# DAC_Interface.net
KiCad netlist of a schematic drawn in Altium Designer
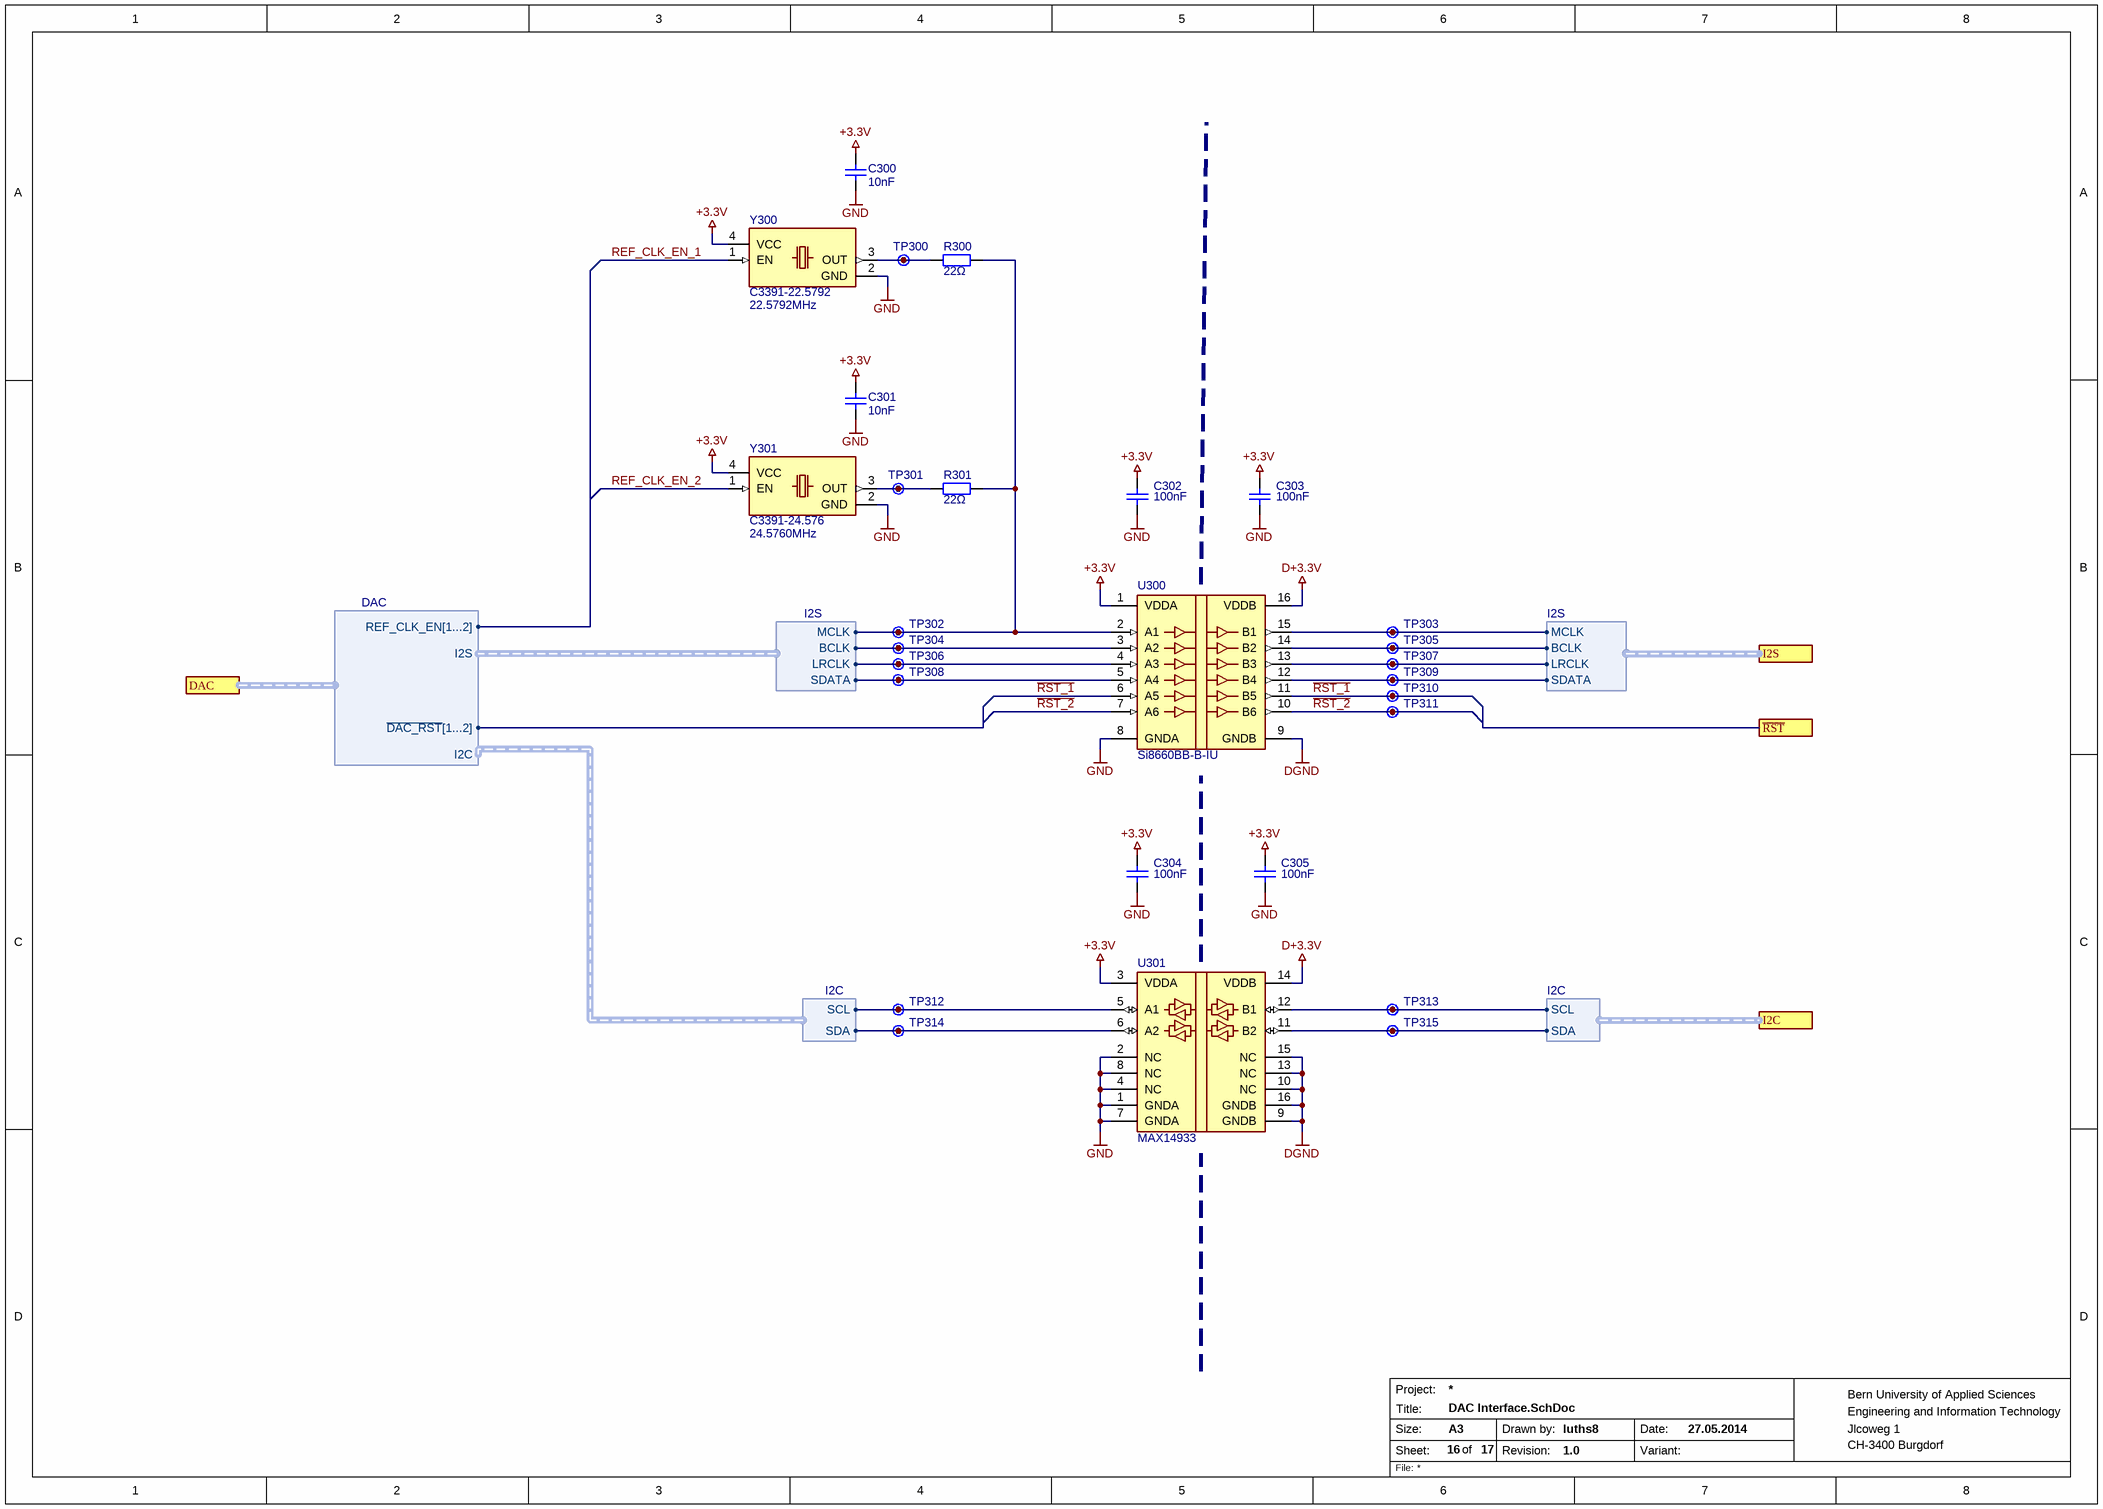
[diagram p0: DAC Interface.SchDoc]

(export (version "E")
  (design (tool "Eeschema 10.0.6"))
  (components
    (comp (ref "C300")
      (value "10nF")
      (footprint "SMD0603CAP")
      (description "Ceramic Capacitor")
      (libsource (lib "Audio-Streamer") (part "Capacitor Ceramic"))
    )
    (comp (ref "C301")
      (value "10nF")
      (footprint "SMD0603CAP")
      (description "Ceramic Capacitor")
      (libsource (lib "Audio-Streamer") (part "Capacitor Ceramic"))
    )
    (comp (ref "C302")
      (value "100nF")
      (footprint "SMD0603CAP")
      (description "Ceramic Capacitor")
      (libsource (lib "Audio-Streamer") (part "Capacitor Ceramic"))
    )
    (comp (ref "C303")
      (value "100nF")
      (footprint "SMD0603CAP")
      (description "Ceramic Capacitor")
      (libsource (lib "Audio-Streamer") (part "Capacitor Ceramic"))
    )
    (comp (ref "C304")
      (value "100nF")
      (footprint "SMD0603CAP")
      (description "Ceramic Capacitor")
      (libsource (lib "Audio-Streamer") (part "Capacitor Ceramic"))
    )
    (comp (ref "C305")
      (value "100nF")
      (footprint "SMD0603CAP")
      (description "Ceramic Capacitor")
      (libsource (lib "Audio-Streamer") (part "Capacitor Ceramic"))
    )
    (comp (ref "R300")
      (value "22Ω")
      (footprint "SMD0603RES")
      (description "Resistor")
      (libsource (lib "Audio-Streamer") (part "Resistor"))
    )
    (comp (ref "R301")
      (value "22Ω")
      (footprint "SMD0603RES")
      (description "Resistor")
      (libsource (lib "Audio-Streamer") (part "Resistor"))
    )
    (comp (ref "TP300")
      (value "Testpoint")
      (footprint "TP")
      (libsource (lib "Audio-Streamer") (part "Testpoint"))
    )
    (comp (ref "TP301")
      (value "Testpoint")
      (footprint "TP")
      (libsource (lib "Audio-Streamer") (part "Testpoint"))
    )
    (comp (ref "TP302")
      (value "Testpoint")
      (footprint "TP")
      (libsource (lib "Audio-Streamer") (part "Testpoint"))
    )
    (comp (ref "TP303")
      (value "Testpoint")
      (footprint "TP")
      (libsource (lib "Audio-Streamer") (part "Testpoint"))
    )
    (comp (ref "TP304")
      (value "Testpoint")
      (footprint "TP")
      (libsource (lib "Audio-Streamer") (part "Testpoint"))
    )
    (comp (ref "TP305")
      (value "Testpoint")
      (footprint "TP")
      (libsource (lib "Audio-Streamer") (part "Testpoint"))
    )
    (comp (ref "TP306")
      (value "Testpoint")
      (footprint "TP")
      (libsource (lib "Audio-Streamer") (part "Testpoint"))
    )
    (comp (ref "TP307")
      (value "Testpoint")
      (footprint "TP")
      (libsource (lib "Audio-Streamer") (part "Testpoint"))
    )
    (comp (ref "TP308")
      (value "Testpoint")
      (footprint "TP")
      (libsource (lib "Audio-Streamer") (part "Testpoint"))
    )
    (comp (ref "TP309")
      (value "Testpoint")
      (footprint "TP")
      (libsource (lib "Audio-Streamer") (part "Testpoint"))
    )
    (comp (ref "TP310")
      (value "Testpoint")
      (footprint "TP")
      (libsource (lib "Audio-Streamer") (part "Testpoint"))
    )
    (comp (ref "TP311")
      (value "Testpoint")
      (footprint "TP")
      (libsource (lib "Audio-Streamer") (part "Testpoint"))
    )
    (comp (ref "TP312")
      (value "Testpoint")
      (footprint "TP")
      (libsource (lib "Audio-Streamer") (part "Testpoint"))
    )
    (comp (ref "TP313")
      (value "Testpoint")
      (footprint "TP")
      (libsource (lib "Audio-Streamer") (part "Testpoint"))
    )
    (comp (ref "TP314")
      (value "Testpoint")
      (footprint "TP")
      (libsource (lib "Audio-Streamer") (part "Testpoint"))
    )
    (comp (ref "TP315")
      (value "Testpoint")
      (footprint "TP")
      (libsource (lib "Audio-Streamer") (part "Testpoint"))
    )
    (comp (ref "U300")
      (value "Si8660BB-B-IU")
      (footprint "SOIC16WIDE")
      (description "Unidirectional digital isolator")
      (libsource (lib "Audio-Streamer") (part "Si8660BB-B-IU"))
    )
    (comp (ref "U301")
      (value "MAX14933")
      (footprint "SOIC16WIDE")
      (description "Bidirectional digital isolator")
      (libsource (lib "Audio-Streamer") (part "MAX14933"))
    )
    (comp (ref "Y300")
      (value "C3391-22.5792")
      (footprint "OSC_CRYSTEK")
      (description "HCMOS Oscillator")
      (fields (field (name "FREQUENCY") "22.5792MHz"))
      (libsource (lib "Audio-Streamer") (part "Oscillator Crystek"))
    )
    (comp (ref "Y301")
      (value "C3391-24.576")
      (footprint "OSC_CRYSTEK")
      (description "HCMOS Oscillator")
      (fields (field (name "FREQUENCY") "24.5760MHz"))
      (libsource (lib "Audio-Streamer") (part "Oscillator Crystek"))
    )
  )
  (nets
    (net (code "5") (name "+3.3V") (class "Default")
      (node (ref "C300") (pin "1") (pinfunction "1_1") (pintype "passive"))
      (node (ref "C301") (pin "1") (pinfunction "1_1") (pintype "passive"))
      (node (ref "C302") (pin "1") (pinfunction "1_1") (pintype "passive"))
      (node (ref "C303") (pin "1") (pinfunction "1_1") (pintype "passive"))
      (node (ref "C304") (pin "1") (pinfunction "1_1") (pintype "passive"))
      (node (ref "C305") (pin "1") (pinfunction "1_1") (pintype "passive"))
      (node (ref "U300") (pin "1") (pinfunction "VDDA_1") (pintype "power_in"))
      (node (ref "U301") (pin "3") (pinfunction "VDDA_3") (pintype "power_in"))
      (node (ref "Y300") (pin "4") (pinfunction "VCC_4") (pintype "power_in"))
      (node (ref "Y301") (pin "4") (pinfunction "VCC_4") (pintype "power_in"))
    )
    (net (code "7") (name "/REF_CLK_EN_1") (class "Default")
      (node (ref "Y300") (pin "1") (pinfunction "EN_1") (pintype "input"))
    )
    (net (code "8") (name "/REF_CLK_EN_2") (class "Default")
      (node (ref "Y301") (pin "1") (pinfunction "EN_1") (pintype "input"))
    )
    (net (code "12") (name "/~{RST_1}") (class "Default")
      (node (ref "TP310") (pin "1") (pinfunction "1_1") (pintype "passive"))
      (node (ref "U300") (pin "11") (pinfunction "B5_11") (pintype "output"))
      (node (ref "U300") (pin "6") (pinfunction "A5_6") (pintype "input"))
    )
    (net (code "13") (name "/~{RST_2}") (class "Default")
      (node (ref "TP311") (pin "1") (pinfunction "1_1") (pintype "passive"))
      (node (ref "U300") (pin "10") (pinfunction "B6_10") (pintype "output"))
      (node (ref "U300") (pin "7") (pinfunction "A6_7") (pintype "input"))
    )
    (net (code "15") (name "D+3.3V") (class "Default")
      (node (ref "U300") (pin "16") (pinfunction "VDDB_16") (pintype "power_in"))
      (node (ref "U301") (pin "14") (pinfunction "VDDB_14") (pintype "power_in"))
    )
    (net (code "16") (name "DGND") (class "Default")
      (node (ref "U300") (pin "9") (pinfunction "GNDB_9") (pintype "power_in"))
      (node (ref "U301") (pin "10") (pinfunction "NC_10") (pintype "passive"))
      (node (ref "U301") (pin "13") (pinfunction "NC_13") (pintype "passive"))
      (node (ref "U301") (pin "15") (pinfunction "NC_15") (pintype "passive"))
      (node (ref "U301") (pin "16") (pinfunction "GNDB_16") (pintype "power_in"))
      (node (ref "U301") (pin "9") (pinfunction "GNDB_9") (pintype "power_in"))
    )
    (net (code "17") (name "GND") (class "Default")
      (node (ref "C300") (pin "2") (pinfunction "q_2") (pintype "passive"))
      (node (ref "C301") (pin "2") (pinfunction "q_2") (pintype "passive"))
      (node (ref "C302") (pin "2") (pinfunction "q_2") (pintype "passive"))
      (node (ref "C303") (pin "2") (pinfunction "q_2") (pintype "passive"))
      (node (ref "C304") (pin "2") (pinfunction "q_2") (pintype "passive"))
      (node (ref "C305") (pin "2") (pinfunction "q_2") (pintype "passive"))
      (node (ref "U300") (pin "8") (pinfunction "GNDA_8") (pintype "power_in"))
      (node (ref "U301") (pin "1") (pinfunction "GNDA_1") (pintype "power_in"))
      (node (ref "U301") (pin "2") (pinfunction "NC_2") (pintype "passive"))
      (node (ref "U301") (pin "4") (pinfunction "NC_4") (pintype "passive"))
      (node (ref "U301") (pin "7") (pinfunction "GNDA_7") (pintype "power_in"))
      (node (ref "U301") (pin "8") (pinfunction "NC_8") (pintype "passive"))
      (node (ref "Y300") (pin "2") (pinfunction "GND_2") (pintype "power_in"))
      (node (ref "Y301") (pin "2") (pinfunction "GND_2") (pintype "power_in"))
    )
    (net (code "18") (name "Net-(U300-A1)") (class "Default")
      (node (ref "R300") (pin "2") (pinfunction "2_2") (pintype "passive"))
      (node (ref "R301") (pin "2") (pinfunction "2_2") (pintype "passive"))
      (node (ref "TP302") (pin "1") (pinfunction "1_1") (pintype "passive"))
      (node (ref "U300") (pin "2") (pinfunction "A1_2") (pintype "input"))
    )
    (net (code "19") (name "Net-(U300-A2)") (class "Default")
      (node (ref "TP304") (pin "1") (pinfunction "1_1") (pintype "passive"))
      (node (ref "U300") (pin "3") (pinfunction "A2_3") (pintype "input"))
    )
    (net (code "20") (name "Net-(U300-A3)") (class "Default")
      (node (ref "TP306") (pin "1") (pinfunction "1_1") (pintype "passive"))
      (node (ref "U300") (pin "4") (pinfunction "A3_4") (pintype "input"))
    )
    (net (code "21") (name "Net-(U300-A4)") (class "Default")
      (node (ref "TP308") (pin "1") (pinfunction "1_1") (pintype "passive"))
      (node (ref "U300") (pin "5") (pinfunction "A4_5") (pintype "input"))
    )
    (net (code "22") (name "Net-(U300-B1)") (class "Default")
      (node (ref "TP303") (pin "1") (pinfunction "1_1") (pintype "passive"))
      (node (ref "U300") (pin "15") (pinfunction "B1_15") (pintype "output"))
    )
    (net (code "23") (name "Net-(U300-B2)") (class "Default")
      (node (ref "TP305") (pin "1") (pinfunction "1_1") (pintype "passive"))
      (node (ref "U300") (pin "14") (pinfunction "B2_14") (pintype "output"))
    )
    (net (code "24") (name "Net-(U300-B3)") (class "Default")
      (node (ref "TP307") (pin "1") (pinfunction "1_1") (pintype "passive"))
      (node (ref "U300") (pin "13") (pinfunction "B3_13") (pintype "output"))
    )
    (net (code "25") (name "Net-(U300-B4)") (class "Default")
      (node (ref "TP309") (pin "1") (pinfunction "1_1") (pintype "passive"))
      (node (ref "U300") (pin "12") (pinfunction "B4_12") (pintype "output"))
    )
    (net (code "26") (name "Net-(U301-A1)") (class "Default")
      (node (ref "TP312") (pin "1") (pinfunction "1_1") (pintype "passive"))
      (node (ref "U301") (pin "5") (pinfunction "A1_5") (pintype "bidirectional"))
    )
    (net (code "27") (name "Net-(U301-A2)") (class "Default")
      (node (ref "TP314") (pin "1") (pinfunction "1_1") (pintype "passive"))
      (node (ref "U301") (pin "6") (pinfunction "A2_6") (pintype "bidirectional"))
    )
    (net (code "28") (name "Net-(U301-B1)") (class "Default")
      (node (ref "TP313") (pin "1") (pinfunction "1_1") (pintype "passive"))
      (node (ref "U301") (pin "12") (pinfunction "B1_12") (pintype "bidirectional"))
    )
    (net (code "29") (name "Net-(U301-B2)") (class "Default")
      (node (ref "TP315") (pin "1") (pinfunction "1_1") (pintype "passive"))
      (node (ref "U301") (pin "11") (pinfunction "B2_11") (pintype "bidirectional"))
    )
    (net (code "30") (name "Net-(Y300-OUT)") (class "Default")
      (node (ref "R300") (pin "1") (pinfunction "1_1") (pintype "passive"))
      (node (ref "TP300") (pin "1") (pinfunction "1_1") (pintype "passive"))
      (node (ref "Y300") (pin "3") (pinfunction "OUT_3") (pintype "output"))
    )
    (net (code "31") (name "Net-(Y301-OUT)") (class "Default")
      (node (ref "R301") (pin "1") (pinfunction "1_1") (pintype "passive"))
      (node (ref "TP301") (pin "1") (pinfunction "1_1") (pintype "passive"))
      (node (ref "Y301") (pin "3") (pinfunction "OUT_3") (pintype "output"))
    )
  )
)
